# Part18_I2C_IO_Expander.net
KiCad netlist of a schematic drawn in Altium Designer
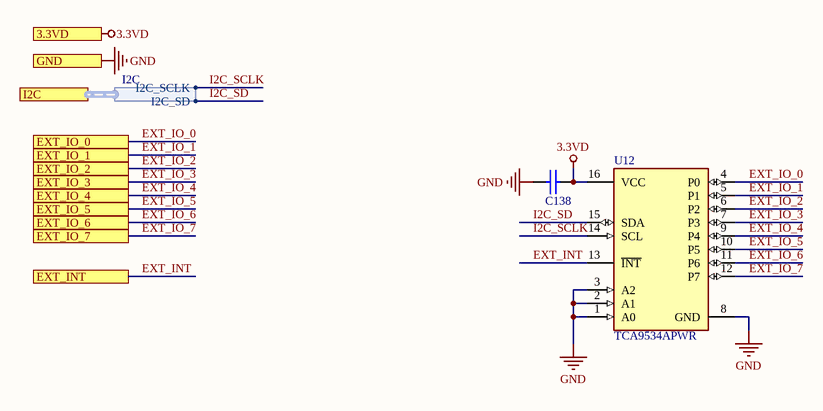
[diagram p0: Part18_I2C_IO_Expander.SchDoc]

(export (version "E")
  (design (tool "Eeschema 10.0.6"))
  (components
    (comp (ref "C138")
      (value "100nF")
      (footprint "0402C")
      (description "无极性电容")
      (libsource (lib "电容") (part "CAP"))
    )
    (comp (ref "U12")
      (value "TCA9534APWR")
      (footprint "FP-PW0016A-MFG")
      (description "IC I/O EXPANDER I2C 8B 16TSSOP")
      (fields
        (field (name "OCTOPART") "https://octopart.com/tca9534apwr-texas+instruments-50333529")
        (field (name "MANUFACTURER") "Texas Instruments")
      )
      (libsource (lib "Altium Content Vault") (part "0b0800cf057530dbd4e48f5dd6c25fb"))
    )
  )
  (nets
    (net (code "2") (name "/EXT_INT") (class "Default")
      (node (ref "U12") (pin "13") (pinfunction "~{INT}_13") (pintype "open_collector"))
    )
    (net (code "3") (name "/EXT_IO_0") (class "Default")
      (node (ref "U12") (pin "4") (pinfunction "P0_4") (pintype "bidirectional"))
    )
    (net (code "4") (name "/EXT_IO_1") (class "Default")
      (node (ref "U12") (pin "5") (pinfunction "P1_5") (pintype "bidirectional"))
    )
    (net (code "5") (name "/EXT_IO_2") (class "Default")
      (node (ref "U12") (pin "6") (pinfunction "P2_6") (pintype "bidirectional"))
    )
    (net (code "6") (name "/EXT_IO_3") (class "Default")
      (node (ref "U12") (pin "7") (pinfunction "P3_7") (pintype "bidirectional"))
    )
    (net (code "7") (name "/EXT_IO_4") (class "Default")
      (node (ref "U12") (pin "9") (pinfunction "P4_9") (pintype "bidirectional"))
    )
    (net (code "8") (name "/EXT_IO_5") (class "Default")
      (node (ref "U12") (pin "10") (pinfunction "P5_10") (pintype "bidirectional"))
    )
    (net (code "9") (name "/EXT_IO_6") (class "Default")
      (node (ref "U12") (pin "11") (pinfunction "P6_11") (pintype "bidirectional"))
    )
    (net (code "10") (name "/EXT_IO_7") (class "Default")
      (node (ref "U12") (pin "12") (pinfunction "P7_12") (pintype "bidirectional"))
    )
    (net (code "11") (name "/I2C_SCLK") (class "Default")
      (node (ref "U12") (pin "14") (pinfunction "SCL_14") (pintype "input"))
    )
    (net (code "12") (name "/I2C_SD") (class "Default")
      (node (ref "U12") (pin "15") (pinfunction "SDA_15") (pintype "bidirectional"))
    )
    (net (code "14") (name "3.3VD") (class "Default")
      (node (ref "C138") (pin "2") (pinfunction "2_2") (pintype "passive"))
      (node (ref "U12") (pin "16") (pinfunction "VCC_16") (pintype "power_in"))
    )
    (net (code "15") (name "GND") (class "Default")
      (node (ref "C138") (pin "1") (pinfunction "1_1") (pintype "passive"))
      (node (ref "U12") (pin "1") (pinfunction "A0_1") (pintype "input"))
      (node (ref "U12") (pin "2") (pinfunction "A1_2") (pintype "input"))
      (node (ref "U12") (pin "3") (pinfunction "A2_3") (pintype "input"))
      (node (ref "U12") (pin "8") (pinfunction "GND_8") (pintype "power_in"))
    )
  )
)
